# 05_interface.net
KiCad netlist of a schematic drawn in Altium Designer
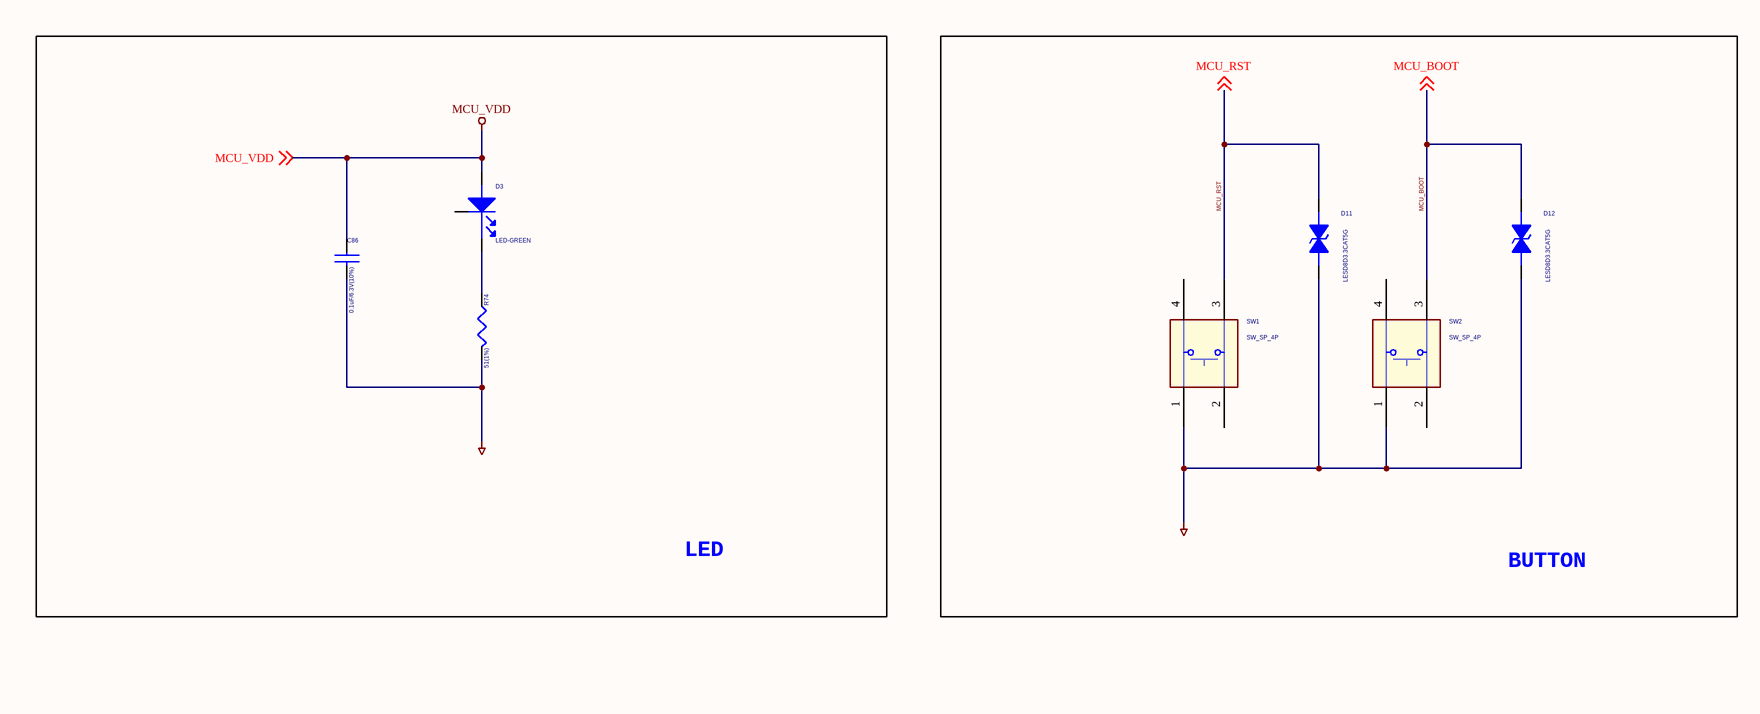
[diagram p0: 05_interface.SchDoc, left]
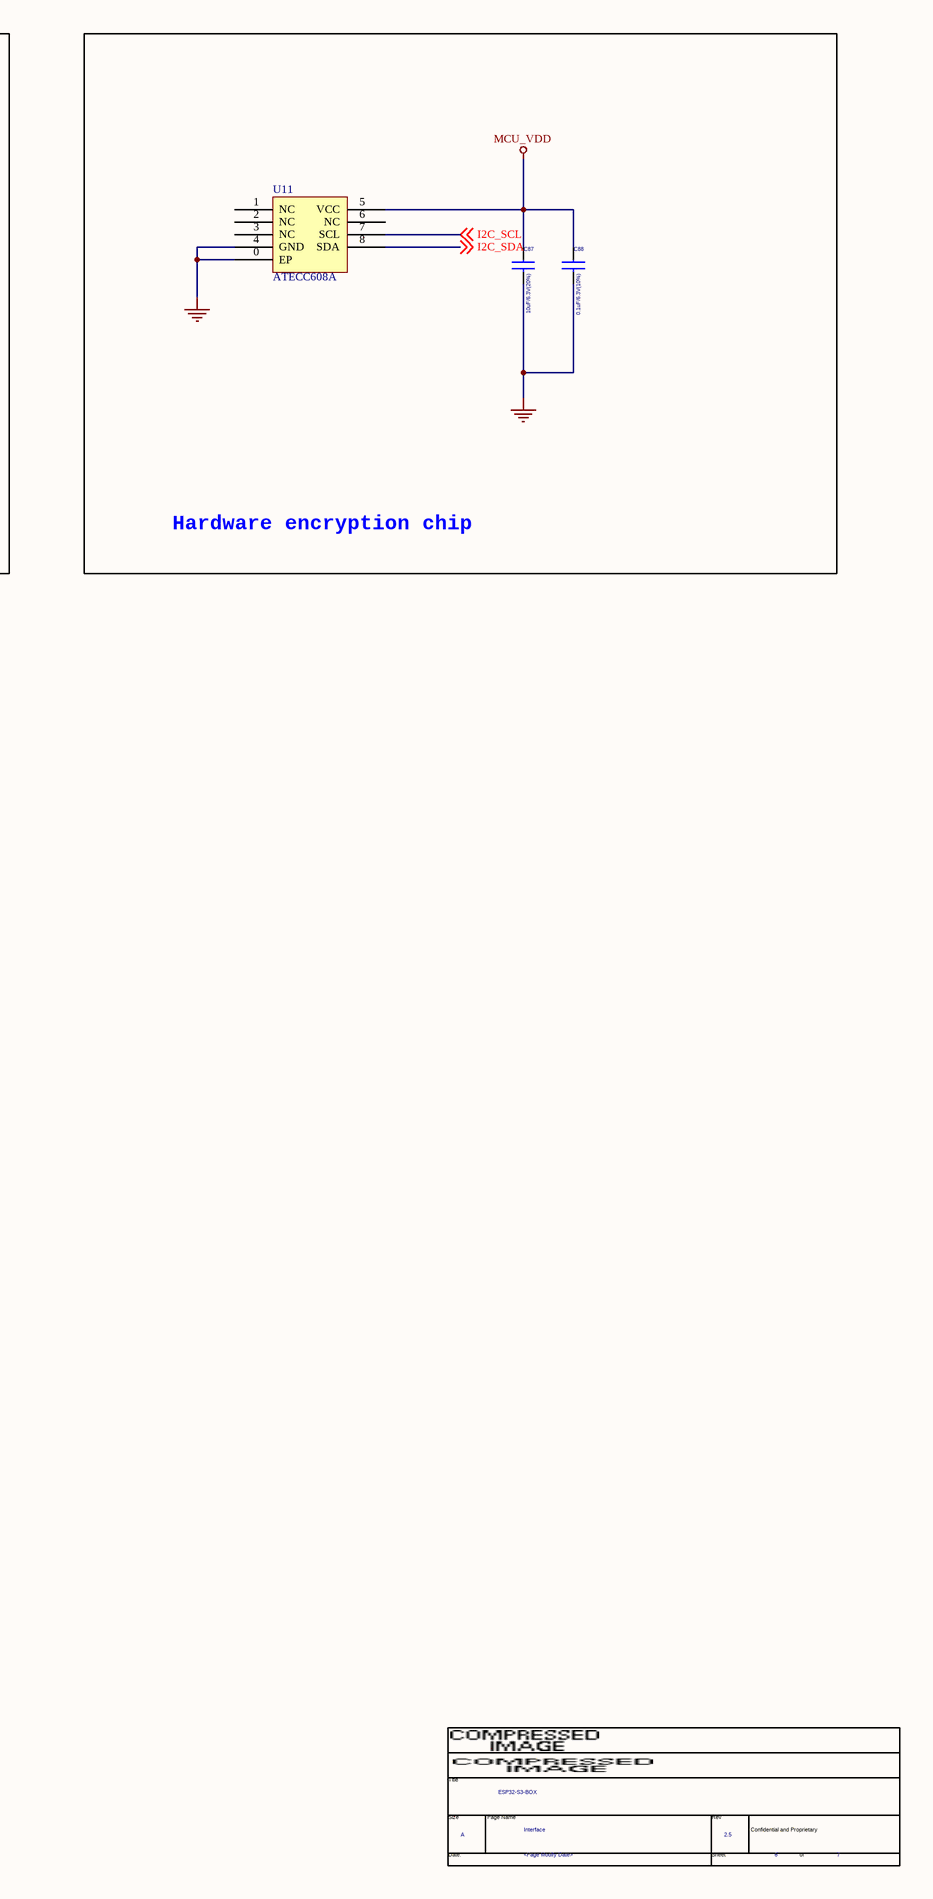
[diagram p1: 05_interface.SchDoc, right]

(export (version "E")
  (design (tool "Eeschema 10.0.6"))
  (components
    (comp (ref "C86")
      (value "0.1uF/6.3V(10%)")
      (footprint "0402_C")
      (fields (field (name "PART NUMBER") "ES11045102620001"))
      (libsource (lib "*") (part "CAPACITOR"))
    )
    (comp (ref "C87")
      (value "10uF/6.3V(20%)")
      (footprint "0402_C")
      (fields (field (name "PART NUMBER") "ES11047102710000"))
      (libsource (lib "*") (part "CAPACITOR"))
    )
    (comp (ref "C88")
      (value "0.1uF/6.3V(10%)")
      (footprint "0402_C")
      (fields (field (name "PART NUMBER") "ES11045102620001"))
      (libsource (lib "*") (part "CAPACITOR"))
    )
    (comp (ref "D3") (value "LED-GREEN") (footprint "0603_L") (libsource (lib "*") (part "LED-GREEN")))
    (comp (ref "D11")
      (value "LESD8D3.3CAT5G")
      (footprint "SOD-882")
      (fields (field (name "PART NUMBER") "ES31320010000000"))
      (libsource (lib "*") (part "DIODE_BI_DIR"))
    )
    (comp (ref "D12")
      (value "LESD8D3.3CAT5G")
      (footprint "SOD-882")
      (fields (field (name "PART NUMBER") "ES31320010000000"))
      (libsource (lib "*") (part "DIODE_BI_DIR"))
    )
    (comp (ref "R74")
      (value "51(1%)")
      (footprint "0201_R")
      (fields (field (name "PART NUMBER") "ES21021510000001"))
      (libsource (lib "*") (part "RESISTOR"))
    )
    (comp (ref "SW1") (value "SW_SP_4P") (footprint "Key3*4*2.5") (libsource (lib "*") (part "SW_SP_4P")))
    (comp (ref "SW2") (value "SW_SP_4P") (footprint "Key3*4*2.5") (libsource (lib "*") (part "SW_SP_4P")))
    (comp (ref "U11")
      (value "ATECC608A")
      (footprint "DFN-8_EP_3x3mm")
      (libsource (lib "supplement") (part "ATECC608A"))
    )
  )
  (nets
    (net (code "1") (name "GND") (class "Default")
      (node (ref "C86") (pin "2") (pinfunction "2_2") (pintype "passive"))
      (node (ref "C87") (pin "2") (pinfunction "2_2") (pintype "passive"))
      (node (ref "C88") (pin "2") (pinfunction "2_2") (pintype "passive"))
      (node (ref "D11") (pin "1") (pinfunction "1_1") (pintype "passive"))
      (node (ref "D12") (pin "1") (pinfunction "1_1") (pintype "passive"))
      (node (ref "R74") (pin "2") (pinfunction "2_2") (pintype "passive"))
      (node (ref "SW1") (pin "1") (pinfunction "1_1") (pintype "passive"))
      (node (ref "SW2") (pin "1") (pinfunction "1_1") (pintype "passive"))
      (node (ref "U11") (pin "0") (pinfunction "EP_0") (pintype "passive"))
      (node (ref "U11") (pin "4") (pinfunction "GND_4") (pintype "passive"))
    )
    (net (code "2") (name "I2C_SCL") (class "Default")
      (node (ref "U11") (pin "7") (pinfunction "SCL_7") (pintype "passive"))
    )
    (net (code "3") (name "I2C_SDA") (class "Default")
      (node (ref "U11") (pin "8") (pinfunction "SDA_8") (pintype "passive"))
    )
    (net (code "4") (name "MCU_BOOT") (class "Default")
      (node (ref "D12") (pin "2") (pinfunction "2_2") (pintype "passive"))
      (node (ref "SW2") (pin "3") (pinfunction "3_3") (pintype "passive"))
    )
    (net (code "5") (name "MCU_RST") (class "Default")
      (node (ref "D11") (pin "2") (pinfunction "2_2") (pintype "passive"))
      (node (ref "SW1") (pin "3") (pinfunction "3_3") (pintype "passive"))
    )
    (net (code "6") (name "MCU_VDD") (class "Default")
      (node (ref "C86") (pin "1") (pinfunction "1_1") (pintype "passive"))
      (node (ref "C87") (pin "1") (pinfunction "1_1") (pintype "passive"))
      (node (ref "C88") (pin "1") (pinfunction "1_1") (pintype "passive"))
      (node (ref "D3") (pin "1") (pinfunction "1_1") (pintype "passive"))
      (node (ref "U11") (pin "5") (pinfunction "VCC_5") (pintype "passive"))
    )
    (net (code "7") (name "Net-(D3-Pad2)") (class "Default")
      (node (ref "D3") (pin "2") (pinfunction "2_2") (pintype "passive"))
      (node (ref "R74") (pin "1") (pinfunction "1_1") (pintype "passive"))
    )
    (net (code "8") (name "unconnected-(D3-Pad3)") (class "Default")
      (node (ref "D3") (pin "3") (pinfunction "3_3") (pintype "passive"))
    )
    (net (code "9") (name "unconnected-(SW1-Pad2)") (class "Default")
      (node (ref "SW1") (pin "2") (pinfunction "2_2") (pintype "passive"))
    )
    (net (code "10") (name "unconnected-(SW1-Pad4)") (class "Default")
      (node (ref "SW1") (pin "4") (pinfunction "4_4") (pintype "passive"))
    )
    (net (code "11") (name "unconnected-(SW2-Pad2)") (class "Default")
      (node (ref "SW2") (pin "2") (pinfunction "2_2") (pintype "passive"))
    )
    (net (code "12") (name "unconnected-(SW2-Pad4)") (class "Default")
      (node (ref "SW2") (pin "4") (pinfunction "4_4") (pintype "passive"))
    )
    (net (code "13") (name "unconnected-(U11-NC-Pad1)") (class "Default")
      (node (ref "U11") (pin "1") (pinfunction "NC_1") (pintype "passive"))
    )
    (net (code "14") (name "unconnected-(U11-NC-Pad2)") (class "Default")
      (node (ref "U11") (pin "2") (pinfunction "NC_2") (pintype "passive"))
    )
    (net (code "15") (name "unconnected-(U11-NC-Pad3)") (class "Default")
      (node (ref "U11") (pin "3") (pinfunction "NC_3") (pintype "passive"))
    )
    (net (code "16") (name "unconnected-(U11-NC-Pad6)") (class "Default")
      (node (ref "U11") (pin "6") (pinfunction "NC_6") (pintype "passive"))
    )
  )
)
